# 1_P1.net
KiCad netlist of a schematic drawn in Altium Designer
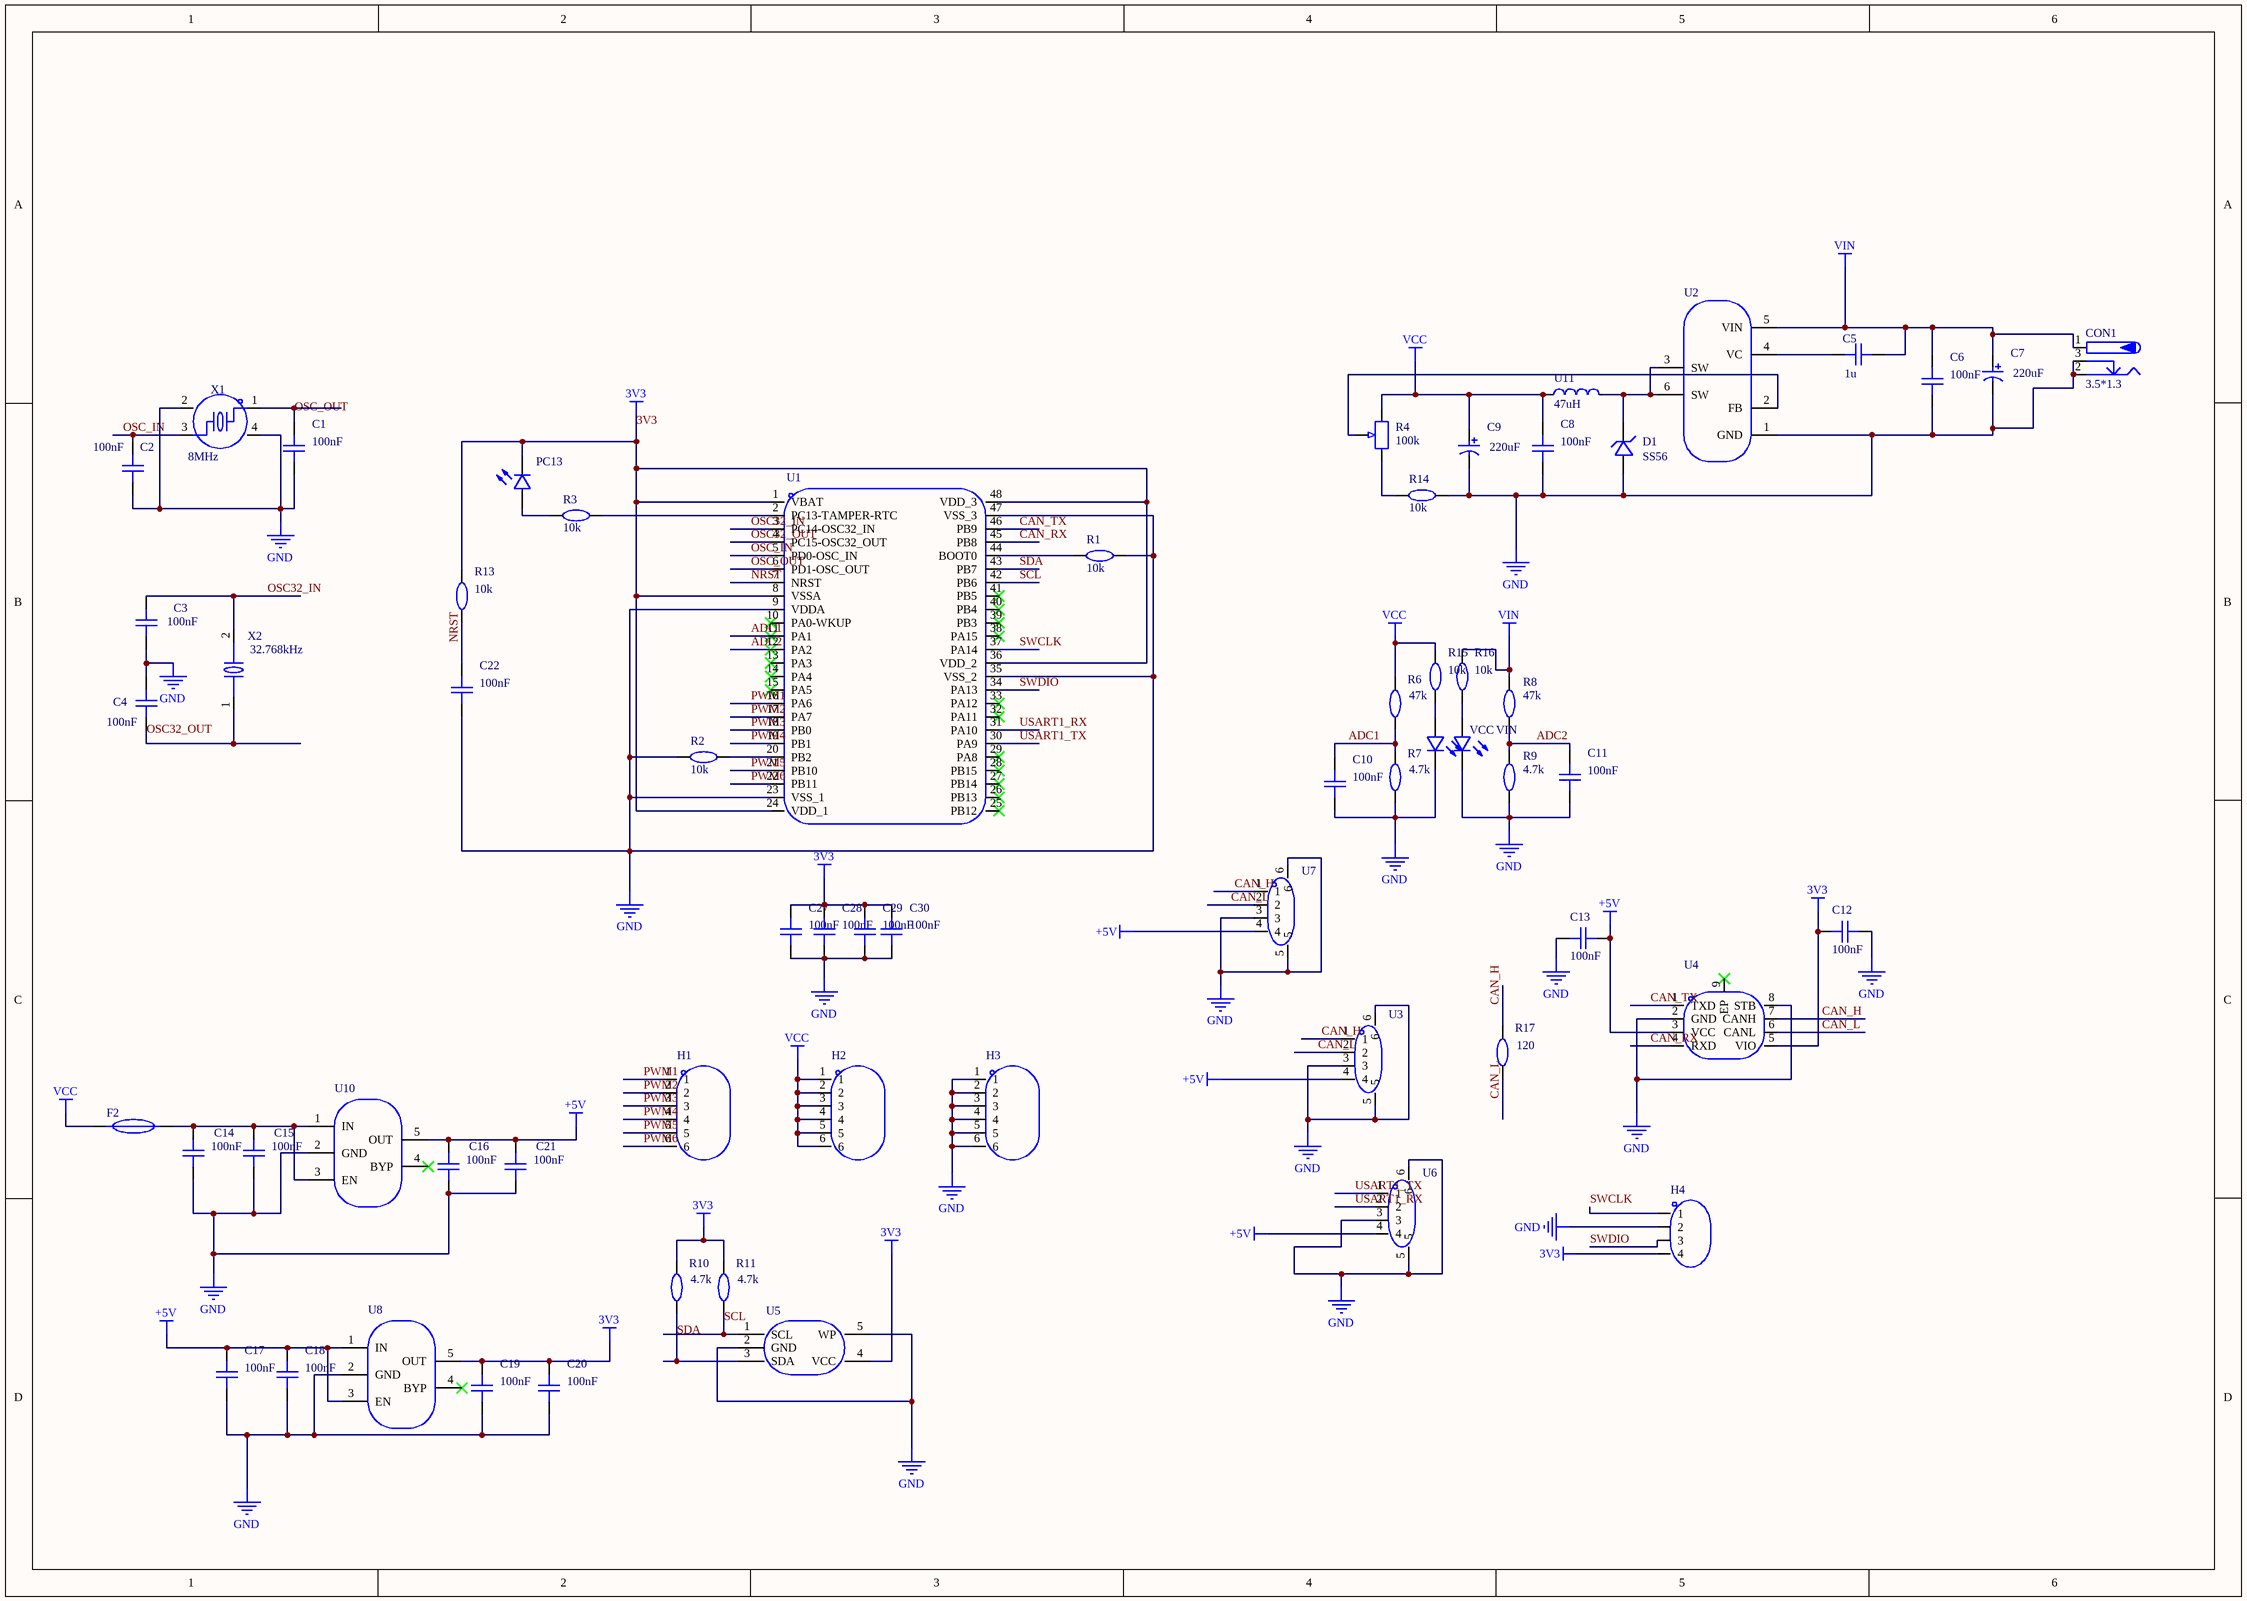
[diagram p0: 1_P1.schdoc]

(export (version "E")
  (design (tool "Eeschema 10.0.6"))
  (components
    (comp (ref "C1")
      (value "100nF")
      (footprint "C0603_M")
      (fields
        (field (name "MANUFACTURER") "YAGEO(国巨)")
        (field (name "MANUFACTURER PART") "CC0603KRX7R9BB104")
        (field (name "TOLERANCE") "±10%")
      )
      (libsource (lib "altium-import") (part "root_1_CC0603KRX7R9BB104_"))
    )
    (comp (ref "C2")
      (value "100nF")
      (footprint "C0603_M")
      (fields
        (field (name "MANUFACTURER") "YAGEO(国巨)")
        (field (name "MANUFACTURER PART") "CC0603KRX7R9BB104")
        (field (name "TOLERANCE") "±10%")
      )
      (libsource (lib "altium-import") (part "root_1_CC0603KRX7R9BB104_"))
    )
    (comp (ref "C3")
      (value "100nF")
      (footprint "C0603_M")
      (fields
        (field (name "MANUFACTURER") "YAGEO(国巨)")
        (field (name "MANUFACTURER PART") "CC0603KRX7R9BB104")
        (field (name "TOLERANCE") "±10%")
      )
      (libsource (lib "altium-import") (part "root_1_CC0603KRX7R9BB104_"))
    )
    (comp (ref "C4")
      (value "100nF")
      (footprint "C0603_M")
      (fields
        (field (name "MANUFACTURER") "YAGEO(国巨)")
        (field (name "MANUFACTURER PART") "CC0603KRX7R9BB104")
        (field (name "TOLERANCE") "±10%")
      )
      (libsource (lib "altium-import") (part "root_3_CC0603KRX7R9BB104_"))
    )
    (comp (ref "C5")
      (value "1u")
      (footprint "C0603_M")
      (fields
        (field (name "MANUFACTURER") "YAGEO(国巨)")
        (field (name "MANUFACTURER PART") "CC0603KRX7R9BB104")
        (field (name "TOLERANCE") "±10%")
      )
      (libsource (lib "altium-import") (part "root_2_CC0603KRX7R9BB104_"))
    )
    (comp (ref "C6")
      (value "100nF")
      (footprint "C0603_M")
      (fields
        (field (name "MANUFACTURER") "YAGEO(国巨)")
        (field (name "MANUFACTURER PART") "CC0603KRX7R9BB104")
        (field (name "TOLERANCE") "±10%")
      )
      (libsource (lib "altium-import") (part "root_1_CC0603KRX7R9BB104_"))
    )
    (comp (ref "C7")
      (value "220uF")
      (footprint "CE D(6.3*5.4)")
      (fields
        (field (name "MANUFACTURER") "rubycon(红宝石)")
        (field (name "MANUFACTURER PART") "50SEV10M6.3X5.5")
        (field (name "TOLERANCE") "±20%")
      )
      (libsource (lib "altium-import") (part "root_3_50SEV10M6.3X5.5_"))
    )
    (comp (ref "C8")
      (value "100nF")
      (footprint "C0603_M")
      (fields
        (field (name "MANUFACTURER") "YAGEO(国巨)")
        (field (name "MANUFACTURER PART") "CC0603KRX7R9BB104")
        (field (name "TOLERANCE") "±10%")
      )
      (libsource (lib "altium-import") (part "root_1_CC0603KRX7R9BB104_"))
    )
    (comp (ref "C9")
      (value "220uF")
      (footprint "CE D(6.3*5.4)")
      (fields
        (field (name "MANUFACTURER") "rubycon(红宝石)")
        (field (name "MANUFACTURER PART") "50SEV10M6.3X5.5")
        (field (name "TOLERANCE") "±20%")
      )
      (libsource (lib "altium-import") (part "root_3_50SEV10M6.3X5.5_"))
    )
    (comp (ref "C10")
      (value "100nF")
      (footprint "C0603_M")
      (fields
        (field (name "MANUFACTURER") "YAGEO(国巨)")
        (field (name "MANUFACTURER PART") "CC0603KRX7R9BB104")
        (field (name "TOLERANCE") "±10%")
      )
      (libsource (lib "altium-import") (part "root_1_CC0603KRX7R9BB104_"))
    )
    (comp (ref "C11")
      (value "100nF")
      (footprint "C0603_M")
      (fields
        (field (name "MANUFACTURER") "YAGEO(国巨)")
        (field (name "MANUFACTURER PART") "CC0603KRX7R9BB104")
        (field (name "TOLERANCE") "±10%")
      )
      (libsource (lib "altium-import") (part "root_1_CC0603KRX7R9BB104_"))
    )
    (comp (ref "C12")
      (value "100nF")
      (footprint "C0603_M")
      (fields
        (field (name "MANUFACTURER") "YAGEO(国巨)")
        (field (name "MANUFACTURER PART") "CC0603KRX7R9BB104")
        (field (name "TOLERANCE") "±10%")
      )
      (libsource (lib "altium-import") (part "root_0_CC0603KRX7R9BB104_"))
    )
    (comp (ref "C13")
      (value "100nF")
      (footprint "C0603_M")
      (fields
        (field (name "MANUFACTURER") "YAGEO(国巨)")
        (field (name "MANUFACTURER PART") "CC0603KRX7R9BB104")
        (field (name "TOLERANCE") "±10%")
      )
      (libsource (lib "altium-import") (part "root_0_CC0603KRX7R9BB104_"))
    )
    (comp (ref "C14")
      (value "100nF")
      (footprint "C0603_M")
      (fields
        (field (name "MANUFACTURER") "YAGEO(国巨)")
        (field (name "MANUFACTURER PART") "CC0603KRX7R9BB104")
        (field (name "TOLERANCE") "±10%")
      )
      (libsource (lib "altium-import") (part "root_1_CC0603KRX7R9BB104_"))
    )
    (comp (ref "C15")
      (value "100nF")
      (footprint "C0603_M")
      (fields
        (field (name "MANUFACTURER") "YAGEO(国巨)")
        (field (name "MANUFACTURER PART") "CC0603KRX7R9BB104")
        (field (name "TOLERANCE") "±10%")
      )
      (libsource (lib "altium-import") (part "root_1_CC0603KRX7R9BB104_"))
    )
    (comp (ref "C16")
      (value "100nF")
      (footprint "C0603_M")
      (fields
        (field (name "MANUFACTURER") "YAGEO(国巨)")
        (field (name "MANUFACTURER PART") "CC0603KRX7R9BB104")
        (field (name "TOLERANCE") "±10%")
      )
      (libsource (lib "altium-import") (part "root_1_CC0603KRX7R9BB104_"))
    )
    (comp (ref "C17")
      (value "100nF")
      (footprint "C0603_M")
      (fields
        (field (name "MANUFACTURER") "YAGEO(国巨)")
        (field (name "MANUFACTURER PART") "CC0603KRX7R9BB104")
        (field (name "TOLERANCE") "±10%")
      )
      (libsource (lib "altium-import") (part "root_1_CC0603KRX7R9BB104_"))
    )
    (comp (ref "C18")
      (value "100nF")
      (footprint "C0603_M")
      (fields
        (field (name "MANUFACTURER") "YAGEO(国巨)")
        (field (name "MANUFACTURER PART") "CC0603KRX7R9BB104")
        (field (name "TOLERANCE") "±10%")
      )
      (libsource (lib "altium-import") (part "root_1_CC0603KRX7R9BB104_"))
    )
    (comp (ref "C19")
      (value "100nF")
      (footprint "C0603_M")
      (fields
        (field (name "MANUFACTURER") "YAGEO(国巨)")
        (field (name "MANUFACTURER PART") "CC0603KRX7R9BB104")
        (field (name "TOLERANCE") "±10%")
      )
      (libsource (lib "altium-import") (part "root_1_CC0603KRX7R9BB104_"))
    )
    (comp (ref "C20")
      (value "100nF")
      (footprint "C0603_M")
      (fields
        (field (name "MANUFACTURER") "YAGEO(国巨)")
        (field (name "MANUFACTURER PART") "CC0603KRX7R9BB104")
        (field (name "TOLERANCE") "±10%")
      )
      (libsource (lib "altium-import") (part "root_1_CC0603KRX7R9BB104_"))
    )
    (comp (ref "C21")
      (value "100nF")
      (footprint "C0603_M")
      (fields
        (field (name "MANUFACTURER") "YAGEO(国巨)")
        (field (name "MANUFACTURER PART") "CC0603KRX7R9BB104")
        (field (name "TOLERANCE") "±10%")
      )
      (libsource (lib "altium-import") (part "root_1_CC0603KRX7R9BB104_"))
    )
    (comp (ref "C22")
      (value "100nF")
      (footprint "C0603_M")
      (fields
        (field (name "MANUFACTURER") "YAGEO(国巨)")
        (field (name "MANUFACTURER PART") "CC0603KRX7R9BB104")
        (field (name "TOLERANCE") "±10%")
      )
      (libsource (lib "altium-import") (part "root_1_CC0603KRX7R9BB104_"))
    )
    (comp (ref "C27")
      (value "100nF")
      (footprint "C0603_M")
      (fields
        (field (name "MANUFACTURER") "YAGEO(国巨)")
        (field (name "MANUFACTURER PART") "CC0603KRX7R9BB104")
        (field (name "TOLERANCE") "±10%")
      )
      (libsource (lib "altium-import") (part "root_1_CC0603KRX7R9BB104_"))
    )
    (comp (ref "C28")
      (value "100nF")
      (footprint "C0603_M")
      (fields
        (field (name "MANUFACTURER") "YAGEO(国巨)")
        (field (name "MANUFACTURER PART") "CC0603KRX7R9BB104")
        (field (name "TOLERANCE") "±10%")
      )
      (libsource (lib "altium-import") (part "root_1_CC0603KRX7R9BB104_"))
    )
    (comp (ref "C29")
      (value "100nF")
      (footprint "C0603_M")
      (fields
        (field (name "MANUFACTURER") "YAGEO(国巨)")
        (field (name "MANUFACTURER PART") "CC0603KRX7R9BB104")
        (field (name "TOLERANCE") "±10%")
      )
      (libsource (lib "altium-import") (part "root_1_CC0603KRX7R9BB104_"))
    )
    (comp (ref "C30")
      (value "100nF")
      (footprint "C0603_M")
      (fields
        (field (name "MANUFACTURER") "YAGEO(国巨)")
        (field (name "MANUFACTURER PART") "CC0603KRX7R9BB104")
        (field (name "TOLERANCE") "±10%")
      )
      (libsource (lib "altium-import") (part "root_1_CC0603KRX7R9BB104_"))
    )
    (comp (ref "CON1")
      (value "3.5*1.3")
      (footprint "DC-005")
      (description "低压电源接口")
      (libsource (lib "0.8 - 以太网-音频-Type-C USB插座") (part "P-DC"))
    )
    (comp (ref "D1")
      (value "~")
      (footprint "SMA")
      (fields (field (name "LCSC PART NAME") "SS56") (field (name "MANUFACTURER PART") "SS56"))
      (libsource (lib "altium-import") (part "root_3_SS56_C379835_"))
    )
    (comp (ref "F2")
      (value "~")
      (footprint "FU 1206")
      (fields (field (name "MANUFACTURER") "JK(金科)") (field (name "MANUFACTURER PART") "JK-nSMD050-30"))
      (libsource (lib "altium-import") (part "root_0_JK-nSMD050-30_"))
    )
    (comp (ref "H1")
      (value "~")
      (footprint "HDR2.54-LI-6P")
      (fields
        (field (name "MANUFACTURER") "Nextron(台湾正凌)")
        (field (name "MANUFACTURER PART") "Z-211-0611-0021-001")
      )
      (libsource (lib "altium-import") (part "root_0_Z-211-0611-0021-001_"))
    )
    (comp (ref "H2")
      (value "~")
      (footprint "HDR2.54-LI-6P")
      (fields
        (field (name "MANUFACTURER") "Nextron(台湾正凌)")
        (field (name "MANUFACTURER PART") "Z-211-0611-0021-001")
      )
      (libsource (lib "altium-import") (part "root_0_Z-211-0611-0021-001_"))
    )
    (comp (ref "H3")
      (value "~")
      (footprint "HDR2.54-LI-6P")
      (fields
        (field (name "MANUFACTURER") "Nextron(台湾正凌)")
        (field (name "MANUFACTURER PART") "Z-211-0611-0021-001")
      )
      (libsource (lib "altium-import") (part "root_0_Z-211-0611-0021-001_"))
    )
    (comp (ref "H4")
      (value "~")
      (footprint "HDR2.54-LI-4P")
      (fields (field (name "MANUFACTURER") "Ckmtw(灿科盟)") (field (name "MANUFACTURER PART") "B-2100S04P-A110"))
      (libsource (lib "altium-import") (part "root_0_B-2100S04P-A110_"))
    )
    (comp (ref "PC13")
      (value "~")
      (footprint "LED0603_R")
      (fields
        (field (name "MANUFACTURER") "EVERLIGHT(台湾亿光)")
        (field (name "MANUFACTURER PART") "19-217/GHC-YR1S2/3T")
      )
      (libsource (lib "altium-import") (part "root_1_19-217/GHC-YR1S2/3T_"))
    )
    (comp (ref "R1")
      (value "10k")
      (footprint "R0603_M")
      (fields
        (field (name "MANUFACTURER") "FH(风华)")
        (field (name "MANUFACTURER PART") "RC-01W1002FT")
        (field (name "TOLERANCE") "±1%")
      )
      (libsource (lib "altium-import") (part "root_0_RC-01W1002FT_"))
    )
    (comp (ref "R2")
      (value "10k")
      (footprint "R0603_M")
      (fields
        (field (name "MANUFACTURER") "FH(风华)")
        (field (name "MANUFACTURER PART") "RC-01W1002FT")
        (field (name "TOLERANCE") "±1%")
      )
      (libsource (lib "altium-import") (part "root_0_RC-01W1002FT_"))
    )
    (comp (ref "R3")
      (value "10k")
      (footprint "R0603_M")
      (fields
        (field (name "MANUFACTURER") "FH(风华)")
        (field (name "MANUFACTURER PART") "RC-01W1002FT")
        (field (name "TOLERANCE") "±1%")
      )
      (libsource (lib "altium-import") (part "root_0_RC-01W1002FT_"))
    )
    (comp (ref "R4")
      (value "100k")
      (footprint "3296W")
      (fields
        (field (name "MANUFACTURER") "BOCHEN(博晨)")
        (field (name "MANUFACTURER PART") "3296W-1-104")
        (field (name "TOLERANCE") "±10%")
      )
      (libsource (lib "altium-import") (part "root_0_3296W-1-104_"))
    )
    (comp (ref "R6")
      (value "47k")
      (footprint "R0603_M")
      (fields
        (field (name "MANUFACTURER") "FH(风华)")
        (field (name "MANUFACTURER PART") "RC-01W1002FT")
        (field (name "TOLERANCE") "±1%")
      )
      (libsource (lib "altium-import") (part "root_1_RC-01W1002FT_"))
    )
    (comp (ref "R7")
      (value "4.7k")
      (footprint "R0603_M")
      (fields
        (field (name "MANUFACTURER") "FH(风华)")
        (field (name "MANUFACTURER PART") "RC-01W1002FT")
        (field (name "TOLERANCE") "±1%")
      )
      (libsource (lib "altium-import") (part "root_1_RC-01W1002FT_"))
    )
    (comp (ref "R8")
      (value "47k")
      (footprint "R0603_M")
      (fields
        (field (name "MANUFACTURER") "FH(风华)")
        (field (name "MANUFACTURER PART") "RC-01W1002FT")
        (field (name "TOLERANCE") "±1%")
      )
      (libsource (lib "altium-import") (part "root_1_RC-01W1002FT_"))
    )
    (comp (ref "R9")
      (value "4.7k")
      (footprint "R0603_M")
      (fields
        (field (name "MANUFACTURER") "FH(风华)")
        (field (name "MANUFACTURER PART") "RC-01W1002FT")
        (field (name "TOLERANCE") "±1%")
      )
      (libsource (lib "altium-import") (part "root_1_RC-01W1002FT_"))
    )
    (comp (ref "R10")
      (value "4.7k")
      (footprint "R0603_M")
      (fields
        (field (name "MANUFACTURER") "EVER OHMS(天二科技)")
        (field (name "MANUFACTURER PART") "TR0603B10K0P0525Z")
        (field (name "TOLERANCE") "±0.1%")
      )
      (libsource (lib "altium-import") (part "root_1_TR0603B10K0P0525Z_"))
    )
    (comp (ref "R11")
      (value "4.7k")
      (footprint "R0603_M")
      (fields
        (field (name "MANUFACTURER") "EVER OHMS(天二科技)")
        (field (name "MANUFACTURER PART") "TR0603B10K0P0525Z")
        (field (name "TOLERANCE") "±0.1%")
      )
      (libsource (lib "altium-import") (part "root_1_TR0603B10K0P0525Z_"))
    )
    (comp (ref "R13")
      (value "10k")
      (footprint "R0603_M")
      (fields
        (field (name "MANUFACTURER") "EVER OHMS(天二科技)")
        (field (name "MANUFACTURER PART") "TR0603B10K0P0525Z")
        (field (name "TOLERANCE") "±0.1%")
      )
      (libsource (lib "altium-import") (part "root_1_TR0603B10K0P0525Z_"))
    )
    (comp (ref "R14")
      (value "10k")
      (footprint "R0603_M")
      (fields
        (field (name "MANUFACTURER") "EVER OHMS(天二科技)")
        (field (name "MANUFACTURER PART") "TR0603B10K0P0525Z")
        (field (name "TOLERANCE") "±0.1%")
      )
      (libsource (lib "altium-import") (part "root_0_TR0603B10K0P0525Z_"))
    )
    (comp (ref "R15")
      (value "10k")
      (footprint "R0603_M")
      (fields
        (field (name "MANUFACTURER") "EVER OHMS(天二科技)")
        (field (name "MANUFACTURER PART") "TR0603B10K0P0525Z")
        (field (name "TOLERANCE") "±0.1%")
      )
      (libsource (lib "altium-import") (part "root_1_TR0603B10K0P0525Z_"))
    )
    (comp (ref "R16")
      (value "10k")
      (footprint "R0603_M")
      (fields
        (field (name "MANUFACTURER") "EVER OHMS(天二科技)")
        (field (name "MANUFACTURER PART") "TR0603B10K0P0525Z")
        (field (name "TOLERANCE") "±0.1%")
      )
      (libsource (lib "altium-import") (part "root_1_TR0603B10K0P0525Z_"))
    )
    (comp (ref "R17")
      (value "120")
      (footprint "R0603_M")
      (fields
        (field (name "MANUFACTURER") "EVER OHMS(天二科技)")
        (field (name "MANUFACTURER PART") "TR0603B10K0P0525Z")
        (field (name "TOLERANCE") "±0.1%")
      )
      (libsource (lib "altium-import") (part "root_1_TR0603B10K0P0525Z_"))
    )
    (comp (ref "U1")
      (value "~")
      (footprint "LQFP48-7*7")
      (fields (field (name "MANUFACTURER") "ST(意法半导体)") (field (name "MANUFACTURER PART") "STM32F103C8T6"))
      (libsource (lib "altium-import") (part "root_0_STM32F103C8T6_"))
    )
    (comp (ref "U2")
      (value "~")
      (footprint "TO263-5")
      (fields (field (name "MANUFACTURER") "XLSEMI(芯龙)") (field (name "MANUFACTURER PART") "XL4015E1"))
      (libsource (lib "altium-import") (part "root_0_XL4015E1_"))
    )
    (comp (ref "U3")
      (value "~")
      (footprint "MX1.25-WT-4P")
      (fields (field (name "MANUFACTURER PART") "XH2.5-4P-LS"))
      (libsource (lib "altium-import") (part "root_0_XH2.5-4P-LS_1_"))
    )
    (comp (ref "U4")
      (value "~")
      (footprint "HVSON-8")
      (fields (field (name "MANUFACTURER") "SIT(芯力特)") (field (name "MANUFACTURER PART") "SIT1042TK/3"))
      (libsource (lib "altium-import") (part "root_0_SIT1042TK/3_"))
    )
    (comp (ref "U5")
      (value "~")
      (footprint "SOT-23-5")
      (fields (field (name "MANUFACTURER") "华虹宏力") (field (name "MANUFACTURER PART") "K24C02"))
      (libsource (lib "altium-import") (part "root_0_K24C02_1_"))
    )
    (comp (ref "U6")
      (value "~")
      (footprint "MX1.25-WT-4P")
      (fields (field (name "MANUFACTURER PART") "XH2.5-4P-LS"))
      (libsource (lib "altium-import") (part "root_0_XH2.5-4P-LS_1_"))
    )
    (comp (ref "U7")
      (value "~")
      (footprint "MX1.25-WT-4P")
      (fields (field (name "MANUFACTURER PART") "XH2.5-4P-LS"))
      (libsource (lib "altium-import") (part "root_0_XH2.5-4P-LS_1_"))
    )
    (comp (ref "U8")
      (value "~")
      (footprint "SOT-23-5")
      (fields
        (field (name "MANUFACTURER") "MaxLinear")
        (field (name "MANUFACTURER PART") "SPX3819M5-L-5-0/TR")
      )
      (libsource (lib "altium-import") (part "root_0_SPX3819M5-L-5-0/TR_"))
    )
    (comp (ref "U10")
      (value "~")
      (footprint "SOT-23-5")
      (fields
        (field (name "MANUFACTURER") "MaxLinear")
        (field (name "MANUFACTURER PART") "SPX3819M5-L-3-3/TR")
      )
      (libsource (lib "altium-import") (part "root_0_SPX3819M5-L-3-3/TR_"))
    )
    (comp (ref "U11")
      (value "47uH")
      (footprint "SLT040125")
      (fields
        (field (name "MANUFACTURER") "Sunltech(韩国顺磁)")
        (field (name "MANUFACTURER PART") "SLT040125T470MUB")
        (field (name "TOLERANCE") "±20%")
      )
      (libsource (lib "altium-import") (part "root_0_SLT040125T470MUB_"))
    )
    (comp (ref "VCC")
      (value "~")
      (footprint "LED0603_R")
      (fields
        (field (name "MANUFACTURER") "EVERLIGHT(台湾亿光)")
        (field (name "MANUFACTURER PART") "19-217/GHC-YR1S2/3T")
      )
      (libsource (lib "altium-import") (part "root_3_19-217/GHC-YR1S2/3T_"))
    )
    (comp (ref "VIN")
      (value "~")
      (footprint "LED0603_R")
      (fields
        (field (name "MANUFACTURER") "EVERLIGHT(台湾亿光)")
        (field (name "MANUFACTURER PART") "19-217/GHC-YR1S2/3T")
      )
      (libsource (lib "altium-import") (part "root_3_19-217/GHC-YR1S2/3T_"))
    )
    (comp (ref "X1")
      (value "8MHz")
      (footprint "OSC-3225-4P")
      (fields (field (name "MANUFACTURER") "YXC扬兴科技") (field (name "MANUFACTURER PART") "X32258MSB4SI"))
      (libsource (lib "altium-import") (part "root_2_X32258MSB4SI_"))
    )
    (comp (ref "X2")
      (value "32.768kHz")
      (footprint "OSC-3215-2P")
      (fields (field (name "MANUFACTURER") "JGHC(晶光华)") (field (name "MANUFACTURER PART") "G3100327072070CY"))
      (libsource (lib "altium-import") (part "root_1_G3100327072070CY_"))
    )
  )
  (nets
    (net (code "1") (name "+5V") (class "Default")
      (node (ref "C13") (pin "2") (pinfunction "2_2") (pintype "passive"))
      (node (ref "C16") (pin "2") (pinfunction "2_2") (pintype "passive"))
      (node (ref "C17") (pin "2") (pinfunction "2_2") (pintype "passive"))
      (node (ref "C18") (pin "2") (pinfunction "2_2") (pintype "passive"))
      (node (ref "C21") (pin "2") (pinfunction "2_2") (pintype "passive"))
      (node (ref "U10") (pin "5") (pinfunction "OUT_5") (pintype "passive"))
      (node (ref "U3") (pin "4") (pinfunction "4_4") (pintype "passive"))
      (node (ref "U4") (pin "3") (pinfunction "VCC_3") (pintype "passive"))
      (node (ref "U6") (pin "4") (pinfunction "4_4") (pintype "passive"))
      (node (ref "U7") (pin "4") (pinfunction "4_4") (pintype "passive"))
      (node (ref "U8") (pin "1") (pinfunction "IN_1") (pintype "passive"))
      (node (ref "U8") (pin "3") (pinfunction "EN_3") (pintype "passive"))
    )
    (net (code "2") (name "/ADC1") (class "Default")
      (node (ref "C10") (pin "2") (pinfunction "2_2") (pintype "passive"))
      (node (ref "R6") (pin "1") (pinfunction "1_1") (pintype "passive"))
      (node (ref "R7") (pin "2") (pinfunction "2_2") (pintype "passive"))
      (node (ref "U1") (pin "11") (pinfunction "PA1_11") (pintype "passive"))
    )
    (net (code "3") (name "/ADC2") (class "Default")
      (node (ref "C11") (pin "2") (pinfunction "2_2") (pintype "passive"))
      (node (ref "R8") (pin "1") (pinfunction "1_1") (pintype "passive"))
      (node (ref "R9") (pin "2") (pinfunction "2_2") (pintype "passive"))
      (node (ref "U1") (pin "12") (pinfunction "PA2_12") (pintype "passive"))
    )
    (net (code "4") (name "/CAN_H") (class "Default")
      (node (ref "R17") (pin "2") (pinfunction "2_2") (pintype "passive"))
      (node (ref "U3") (pin "1") (pinfunction "1_1") (pintype "passive"))
      (node (ref "U4") (pin "7") (pinfunction "CANH_7") (pintype "passive"))
      (node (ref "U7") (pin "1") (pinfunction "1_1") (pintype "passive"))
    )
    (net (code "5") (name "/CAN_L") (class "Default")
      (node (ref "R17") (pin "1") (pinfunction "1_1") (pintype "passive"))
      (node (ref "U3") (pin "2") (pinfunction "2_2") (pintype "passive"))
      (node (ref "U4") (pin "6") (pinfunction "CANL_6") (pintype "passive"))
      (node (ref "U7") (pin "2") (pinfunction "2_2") (pintype "passive"))
    )
    (net (code "6") (name "/CAN_RX") (class "Default")
      (node (ref "U1") (pin "45") (pinfunction "PB8_45") (pintype "passive"))
      (node (ref "U4") (pin "4") (pinfunction "RXD_4") (pintype "passive"))
    )
    (net (code "7") (name "/CAN_TX") (class "Default")
      (node (ref "U1") (pin "46") (pinfunction "PB9_46") (pintype "passive"))
      (node (ref "U4") (pin "1") (pinfunction "TXD_1") (pintype "passive"))
    )
    (net (code "8") (name "/NRST") (class "Default")
      (node (ref "C22") (pin "2") (pinfunction "2_2") (pintype "passive"))
      (node (ref "R13") (pin "1") (pinfunction "1_1") (pintype "passive"))
      (node (ref "U1") (pin "7") (pinfunction "NRST_7") (pintype "passive"))
    )
    (net (code "9") (name "/OSC32_IN") (class "Default")
      (node (ref "C3") (pin "2") (pinfunction "2_2") (pintype "passive"))
      (node (ref "U1") (pin "3") (pinfunction "PC14-OSC32_IN_3") (pintype "passive"))
      (node (ref "X2") (pin "2") (pinfunction "2_2") (pintype "passive"))
    )
    (net (code "10") (name "/OSC32_OUT") (class "Default")
      (node (ref "C4") (pin "2") (pinfunction "2_2") (pintype "passive"))
      (node (ref "U1") (pin "4") (pinfunction "PC15-OSC32_OUT_4") (pintype "passive"))
      (node (ref "X2") (pin "1") (pinfunction "1_1") (pintype "passive"))
    )
    (net (code "11") (name "/OSC_IN") (class "Default")
      (node (ref "C2") (pin "2") (pinfunction "2_2") (pintype "passive"))
      (node (ref "U1") (pin "5") (pinfunction "PD0-OSC_IN_5") (pintype "passive"))
      (node (ref "X1") (pin "3") (pinfunction "3_3") (pintype "passive"))
    )
    (net (code "12") (name "/OSC_OUT") (class "Default")
      (node (ref "C1") (pin "2") (pinfunction "2_2") (pintype "passive"))
      (node (ref "U1") (pin "6") (pinfunction "PD1-OSC_OUT_6") (pintype "passive"))
      (node (ref "X1") (pin "1") (pinfunction "1_1") (pintype "passive"))
    )
    (net (code "13") (name "/PWM1") (class "Default")
      (node (ref "H1") (pin "1") (pinfunction "1_1") (pintype "passive"))
      (node (ref "U1") (pin "16") (pinfunction "PA6_16") (pintype "passive"))
    )
    (net (code "14") (name "/PWM2") (class "Default")
      (node (ref "H1") (pin "2") (pinfunction "2_2") (pintype "passive"))
      (node (ref "U1") (pin "17") (pinfunction "PA7_17") (pintype "passive"))
    )
    (net (code "15") (name "/PWM3") (class "Default")
      (node (ref "H1") (pin "3") (pinfunction "3_3") (pintype "passive"))
      (node (ref "U1") (pin "18") (pinfunction "PB0_18") (pintype "passive"))
    )
    (net (code "16") (name "/PWM4") (class "Default")
      (node (ref "H1") (pin "4") (pinfunction "4_4") (pintype "passive"))
      (node (ref "U1") (pin "19") (pinfunction "PB1_19") (pintype "passive"))
    )
    (net (code "17") (name "/PWM5") (class "Default")
      (node (ref "H1") (pin "5") (pinfunction "5_5") (pintype "passive"))
      (node (ref "U1") (pin "21") (pinfunction "PB10_21") (pintype "passive"))
    )
    (net (code "18") (name "/PWM6") (class "Default")
      (node (ref "H1") (pin "6") (pinfunction "6_6") (pintype "passive"))
      (node (ref "U1") (pin "22") (pinfunction "PB11_22") (pintype "passive"))
    )
    (net (code "19") (name "/SCL") (class "Default")
      (node (ref "R11") (pin "1") (pinfunction "1_1") (pintype "passive"))
      (node (ref "U1") (pin "42") (pinfunction "PB6_42") (pintype "passive"))
      (node (ref "U5") (pin "1") (pinfunction "SCL_1") (pintype "passive"))
    )
    (net (code "20") (name "/SDA") (class "Default")
      (node (ref "R10") (pin "1") (pinfunction "1_1") (pintype "passive"))
      (node (ref "U1") (pin "43") (pinfunction "PB7_43") (pintype "passive"))
      (node (ref "U5") (pin "3") (pinfunction "SDA_3") (pintype "passive"))
    )
    (net (code "21") (name "/SWCLK") (class "Default")
      (node (ref "H4") (pin "1") (pinfunction "1_1") (pintype "passive"))
      (node (ref "U1") (pin "37") (pinfunction "PA14_37") (pintype "passive"))
    )
    (net (code "22") (name "/SWDIO") (class "Default")
      (node (ref "H4") (pin "3") (pinfunction "3_3") (pintype "passive"))
      (node (ref "U1") (pin "34") (pinfunction "PA13_34") (pintype "passive"))
    )
    (net (code "23") (name "/USART1_RX") (class "Default")
      (node (ref "U1") (pin "31") (pinfunction "PA10_31") (pintype "passive"))
      (node (ref "U6") (pin "2") (pinfunction "2_2") (pintype "passive"))
    )
    (net (code "24") (name "/USART1_TX") (class "Default")
      (node (ref "U1") (pin "30") (pinfunction "PA9_30") (pintype "passive"))
      (node (ref "U6") (pin "1") (pinfunction "1_1") (pintype "passive"))
    )
    (net (code "25") (name "3V3") (class "Default")
      (node (ref "C12") (pin "1") (pinfunction "1_1") (pintype "passive"))
      (node (ref "C19") (pin "2") (pinfunction "2_2") (pintype "passive"))
      (node (ref "C20") (pin "2") (pinfunction "2_2") (pintype "passive"))
      (node (ref "C27") (pin "2") (pinfunction "2_2") (pintype "passive"))
      (node (ref "C28") (pin "2") (pinfunction "2_2") (pintype "passive"))
      (node (ref "C29") (pin "2") (pinfunction "2_2") (pintype "passive"))
      (node (ref "C30") (pin "2") (pinfunction "2_2") (pintype "passive"))
      (node (ref "H4") (pin "4") (pinfunction "4_4") (pintype "passive"))
      (node (ref "PC13") (pin "2") (pinfunction "C_2") (pintype "passive"))
      (node (ref "R10") (pin "2") (pinfunction "2_2") (pintype "passive"))
      (node (ref "R11") (pin "2") (pinfunction "2_2") (pintype "passive"))
      (node (ref "R13") (pin "2") (pinfunction "2_2") (pintype "passive"))
      (node (ref "U1") (pin "1") (pinfunction "VBAT_1") (pintype "passive"))
      (node (ref "U1") (pin "24") (pinfunction "VDD_1_24") (pintype "passive"))
      (node (ref "U1") (pin "36") (pinfunction "VDD_2_36") (pintype "passive"))
      (node (ref "U1") (pin "48") (pinfunction "VDD_3_48") (pintype "passive"))
      (node (ref "U1") (pin "8") (pinfunction "VSSA_8") (pintype "passive"))
      (node (ref "U4") (pin "5") (pinfunction "VIO_5") (pintype "passive"))
      (node (ref "U5") (pin "4") (pinfunction "VCC_4") (pintype "passive"))
      (node (ref "U8") (pin "5") (pinfunction "OUT_5") (pintype "passive"))
    )
    (net (code "26") (name "GND") (class "Default")
      (node (ref "C1") (pin "1") (pinfunction "1_1") (pintype "passive"))
      (node (ref "C10") (pin "1") (pinfunction "1_1") (pintype "passive"))
      (node (ref "C11") (pin "1") (pinfunction "1_1") (pintype "passive"))
      (node (ref "C12") (pin "2") (pinfunction "2_2") (pintype "passive"))
      (node (ref "C13") (pin "1") (pinfunction "1_1") (pintype "passive"))
      (node (ref "C14") (pin "1") (pinfunction "1_1") (pintype "passive"))
      (node (ref "C15") (pin "1") (pinfunction "1_1") (pintype "passive"))
      (node (ref "C16") (pin "1") (pinfunction "1_1") (pintype "passive"))
      (node (ref "C17") (pin "1") (pinfunction "1_1") (pintype "passive"))
      (node (ref "C18") (pin "1") (pinfunction "1_1") (pintype "passive"))
      (node (ref "C19") (pin "1") (pinfunction "1_1") (pintype "passive"))
      (node (ref "C2") (pin "1") (pinfunction "1_1") (pintype "passive"))
      (node (ref "C20") (pin "1") (pinfunction "1_1") (pintype "passive"))
      (node (ref "C21") (pin "1") (pinfunction "1_1") (pintype "passive"))
      (node (ref "C22") (pin "1") (pinfunction "1_1") (pintype "passive"))
      (node (ref "C27") (pin "1") (pinfunction "1_1") (pintype "passive"))
      (node (ref "C28") (pin "1") (pinfunction "1_1") (pintype "passive"))
      (node (ref "C29") (pin "1") (pinfunction "1_1") (pintype "passive"))
      (node (ref "C3") (pin "1") (pinfunction "1_1") (pintype "passive"))
      (node (ref "C30") (pin "1") (pinfunction "1_1") (pintype "passive"))
      (node (ref "C4") (pin "1") (pinfunction "1_1") (pintype "passive"))
      (node (ref "C6") (pin "1") (pinfunction "1_1") (pintype "passive"))
      (node (ref "C7") (pin "2") (pinfunction "2_2") (pintype "passive"))
      (node (ref "C8") (pin "1") (pinfunction "1_1") (pintype "passive"))
      (node (ref "C9") (pin "2") (pinfunction "2_2") (pintype "passive"))
      (node (ref "CON1") (pin "2") (pintype "power_in"))
      (node (ref "CON1") (pin "3") (pintype "power_in"))
      (node (ref "D1") (pin "2") (pinfunction "A_2") (pintype "passive"))
      (node (ref "H3") (pin "1") (pinfunction "1_1") (pintype "passive"))
      (node (ref "H3") (pin "2") (pinfunction "2_2") (pintype "passive"))
      (node (ref "H3") (pin "3") (pinfunction "3_3") (pintype "passive"))
      (node (ref "H3") (pin "4") (pinfunction "4_4") (pintype "passive"))
      (node (ref "H3") (pin "5") (pinfunction "5_5") (pintype "passive"))
      (node (ref "H3") (pin "6") (pinfunction "6_6") (pintype "passive"))
      (node (ref "H4") (pin "2") (pinfunction "2_2") (pintype "passive"))
      (node (ref "R1") (pin "2") (pinfunction "2_2") (pintype "passive"))
      (node (ref "R14") (pin "2") (pinfunction "2_2") (pintype "passive"))
      (node (ref "R2") (pin "1") (pinfunction "1_1") (pintype "passive"))
      (node (ref "R7") (pin "1") (pinfunction "1_1") (pintype "passive"))
      (node (ref "R9") (pin "1") (pinfunction "1_1") (pintype "passive"))
      (node (ref "U1") (pin "23") (pinfunction "VSS_1_23") (pintype "passive"))
      (node (ref "U1") (pin "35") (pinfunction "VSS_2_35") (pintype "passive"))
      (node (ref "U1") (pin "47") (pinfunction "VSS_3_47") (pintype "passive"))
      (node (ref "U1") (pin "9") (pinfunction "VDDA_9") (pintype "passive"))
      (node (ref "U10") (pin "2") (pinfunction "GND_2") (pintype "passive"))
      (node (ref "U2") (pin "1") (pinfunction "GND_1") (pintype "passive"))
      (node (ref "U3") (pin "3") (pinfunction "3_3") (pintype "passive"))
      (node (ref "U3") (pin "5") (pinfunction "5_5") (pintype "passive"))
      (node (ref "U3") (pin "6") (pinfunction "6_6") (pintype "passive"))
      (node (ref "U4") (pin "2") (pinfunction "GND_2") (pintype "passive"))
      (node (ref "U4") (pin "8") (pinfunction "STB_8") (pintype "passive"))
      (node (ref "U5") (pin "2") (pinfunction "GND_2") (pintype "passive"))
      (node (ref "U5") (pin "5") (pinfunction "WP_5") (pintype "passive"))
      (node (ref "U6") (pin "3") (pinfunction "3_3") (pintype "passive"))
      (node (ref "U6") (pin "5") (pinfunction "5_5") (pintype "passive"))
      (node (ref "U6") (pin "6") (pinfunction "6_6") (pintype "passive"))
      (node (ref "U7") (pin "3") (pinfunction "3_3") (pintype "passive"))
      (node (ref "U7") (pin "5") (pinfunction "5_5") (pintype "passive"))
      (node (ref "U7") (pin "6") (pinfunction "6_6") (pintype "passive"))
      (node (ref "U8") (pin "2") (pinfunction "GND_2") (pintype "passive"))
      (node (ref "VCC") (pin "2") (pinfunction "C_2") (pintype "passive"))
      (node (ref "VIN") (pin "2") (pinfunction "C_2") (pintype "passive"))
      (node (ref "X1") (pin "2") (pinfunction "GND_2") (pintype "passive"))
      (node (ref "X1") (pin "4") (pinfunction "GND_4") (pintype "passive"))
    )
    (net (code "27") (name "Net-(D1-C)") (class "Default")
      (node (ref "D1") (pin "1") (pinfunction "C_1") (pintype "passive"))
      (node (ref "U11") (pin "2") (pinfunction "2_2") (pintype "passive"))
      (node (ref "U2") (pin "3") (pinfunction "SW_3") (pintype "passive"))
      (node (ref "U2") (pin "6") (pinfunction "SW_6") (pintype "passive"))
    )
    (net (code "28") (name "Net-(PC13-A)") (class "Default")
      (node (ref "PC13") (pin "1") (pinfunction "A_1") (pintype "passive"))
      (node (ref "R3") (pin "1") (pinfunction "1_1") (pintype "passive"))
    )
    (net (code "29") (name "Net-(R14-Pad1)") (class "Default")
      (node (ref "R14") (pin "1") (pinfunction "1_1") (pintype "passive"))
      (node (ref "R4") (pin "1") (pinfunction "1_1") (pintype "passive"))
    )
    (net (code "30") (name "Net-(U1-BOOT0)") (class "Default")
      (node (ref "R1") (pin "1") (pinfunction "1_1") (pintype "passive"))
      (node (ref "U1") (pin "44") (pinfunction "BOOT0_44") (pintype "passive"))
    )
    (net (code "31") (name "Net-(U1-PB2)") (class "Default")
      (node (ref "R2") (pin "2") (pinfunction "2_2") (pintype "passive"))
      (node (ref "U1") (pin "20") (pinfunction "PB2_20") (pintype "passive"))
    )
    (net (code "32") (name "Net-(U1-PC13-TAMPER-RTC)") (class "Default")
      (node (ref "R3") (pin "2") (pinfunction "2_2") (pintype "passive"))
      (node (ref "U1") (pin "2") (pinfunction "PC13-TAMPER-RTC_2") (pintype "passive"))
    )
    (net (code "33") (name "Net-(U2-FB)") (class "Default")
      (node (ref "R4") (pin "2") (pinfunction "2_2") (pintype "passive"))
      (node (ref "U2") (pin "2") (pinfunction "FB_2") (pintype "passive"))
    )
    (net (code "34") (name "Net-(U2-VC)") (class "Default")
      (node (ref "C5") (pin "2") (pinfunction "2_2") (pintype "passive"))
      (node (ref "U2") (pin "4") (pinfunction "VC_4") (pintype "passive"))
    )
    (net (code "35") (name "Net-(U10-EN)") (class "Default")
      (node (ref "C14") (pin "2") (pinfunction "2_2") (pintype "passive"))
      (node (ref "C15") (pin "2") (pinfunction "2_2") (pintype "passive"))
      (node (ref "F2") (pin "2") (pinfunction "2_2") (pintype "passive"))
      (node (ref "U10") (pin "1") (pinfunction "IN_1") (pintype "passive"))
      (node (ref "U10") (pin "3") (pinfunction "EN_3") (pintype "passive"))
    )
    (net (code "36") (name "Net-(VCC-A)") (class "Default")
      (node (ref "R15") (pin "1") (pinfunction "1_1") (pintype "passive"))
      (node (ref "VCC") (pin "1") (pinfunction "A_1") (pintype "passive"))
    )
    (net (code "37") (name "Net-(VIN-A)") (class "Default")
      (node (ref "R16") (pin "1") (pinfunction "1_1") (pintype "passive"))
      (node (ref "VIN") (pin "1") (pinfunction "A_1") (pintype "passive"))
    )
    (net (code "38") (name "VCC") (class "Default")
      (node (ref "C8") (pin "2") (pinfunction "2_2") (pintype "passive"))
      (node (ref "C9") (pin "1") (pinfunction "1_1") (pintype "passive"))
      (node (ref "F2") (pin "1") (pinfunction "1_1") (pintype "passive"))
      (node (ref "H2") (pin "1") (pinfunction "1_1") (pintype "passive"))
      (node (ref "H2") (pin "2") (pinfunction "2_2") (pintype "passive"))
      (node (ref "H2") (pin "3") (pinfunction "3_3") (pintype "passive"))
      (node (ref "H2") (pin "4") (pinfunction "4_4") (pintype "passive"))
      (node (ref "H2") (pin "5") (pinfunction "5_5") (pintype "passive"))
      (node (ref "H2") (pin "6") (pinfunction "6_6") (pintype "passive"))
      (node (ref "R15") (pin "2") (pinfunction "2_2") (pintype "passive"))
      (node (ref "R4") (pin "3") (pinfunction "3_3") (pintype "passive"))
      (node (ref "R6") (pin "2") (pinfunction "2_2") (pintype "passive"))
      (node (ref "U11") (pin "1") (pinfunction "1_1") (pintype "passive"))
    )
    (net (code "39") (name "VIN") (class "Default")
      (node (ref "C5") (pin "1") (pinfunction "1_1") (pintype "passive"))
      (node (ref "C6") (pin "2") (pinfunction "2_2") (pintype "passive"))
      (node (ref "C7") (pin "1") (pinfunction "1_1") (pintype "passive"))
      (node (ref "CON1") (pin "1") (pintype "power_in"))
      (node (ref "R16") (pin "2") (pinfunction "2_2") (pintype "passive"))
      (node (ref "R8") (pin "2") (pinfunction "2_2") (pintype "passive"))
      (node (ref "U2") (pin "5") (pinfunction "VIN_5") (pintype "passive"))
    )
    (net (code "40") (name "unconnected-(U1-PA0-WKUP-Pad10)") (class "Default")
      (node (ref "U1") (pin "10") (pinfunction "PA0-WKUP_10") (pintype "passive+no_connect"))
    )
    (net (code "41") (name "unconnected-(U1-PA3-Pad13)") (class "Default")
      (node (ref "U1") (pin "13") (pinfunction "PA3_13") (pintype "passive+no_connect"))
    )
    (net (code "42") (name "unconnected-(U1-PA4-Pad14)") (class "Default")
      (node (ref "U1") (pin "14") (pinfunction "PA4_14") (pintype "passive+no_connect"))
    )
    (net (code "43") (name "unconnected-(U1-PA5-Pad15)") (class "Default")
      (node (ref "U1") (pin "15") (pinfunction "PA5_15") (pintype "passive+no_connect"))
    )
    (net (code "44") (name "unconnected-(U1-PA8-Pad29)") (class "Default")
      (node (ref "U1") (pin "29") (pinfunction "PA8_29") (pintype "passive+no_connect"))
    )
    (net (code "45") (name "unconnected-(U1-PA11-Pad32)") (class "Default")
      (node (ref "U1") (pin "32") (pinfunction "PA11_32") (pintype "passive+no_connect"))
    )
    (net (code "46") (name "unconnected-(U1-PA12-Pad33)") (class "Default")
      (node (ref "U1") (pin "33") (pinfunction "PA12_33") (pintype "passive+no_connect"))
    )
    (net (code "47") (name "unconnected-(U1-PA15-Pad38)") (class "Default")
      (node (ref "U1") (pin "38") (pinfunction "PA15_38") (pintype "passive+no_connect"))
    )
    (net (code "48") (name "unconnected-(U1-PB3-Pad39)") (class "Default")
      (node (ref "U1") (pin "39") (pinfunction "PB3_39") (pintype "passive+no_connect"))
    )
    (net (code "49") (name "unconnected-(U1-PB4-Pad40)") (class "Default")
      (node (ref "U1") (pin "40") (pinfunction "PB4_40") (pintype "passive+no_connect"))
    )
    (net (code "50") (name "unconnected-(U1-PB5-Pad41)") (class "Default")
      (node (ref "U1") (pin "41") (pinfunction "PB5_41") (pintype "passive+no_connect"))
    )
    (net (code "51") (name "unconnected-(U1-PB12-Pad25)") (class "Default")
      (node (ref "U1") (pin "25") (pinfunction "PB12_25") (pintype "passive+no_connect"))
    )
    (net (code "52") (name "unconnected-(U1-PB13-Pad26)") (class "Default")
      (node (ref "U1") (pin "26") (pinfunction "PB13_26") (pintype "passive+no_connect"))
    )
    (net (code "53") (name "unconnected-(U1-PB14-Pad27)") (class "Default")
      (node (ref "U1") (pin "27") (pinfunction "PB14_27") (pintype "passive+no_connect"))
    )
    (net (code "54") (name "unconnected-(U1-PB15-Pad28)") (class "Default")
      (node (ref "U1") (pin "28") (pinfunction "PB15_28") (pintype "passive+no_connect"))
    )
    (net (code "55") (name "unconnected-(U4-EP-Pad9)") (class "Default")
      (node (ref "U4") (pin "9") (pinfunction "EP_9") (pintype "passive+no_connect"))
    )
    (net (code "56") (name "unconnected-(U8-BYP-Pad4)") (class "Default")
      (node (ref "U8") (pin "4") (pinfunction "BYP_4") (pintype "passive+no_connect"))
    )
    (net (code "57") (name "unconnected-(U10-BYP-Pad4)") (class "Default")
      (node (ref "U10") (pin "4") (pinfunction "BYP_4") (pintype "passive+no_connect"))
    )
  )
)
